# breakout.net
KiCad netlist of a schematic drawn in EAGLE
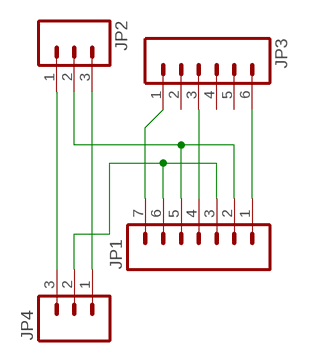
[diagram p0: schematic, sheet 1]

(export (version "E")
  (design (tool "Eeschema 10.0.6"))
  (components
    (comp (ref "JP1")
      (value "M07")
      (footprint "eagle-import:1X07")
      (libsource (lib "eagle-import") (part "M07"))
    )
    (comp (ref "JP2")
      (value "M03PTH")
      (footprint "eagle-import:1X03")
      (libsource (lib "eagle-import") (part "M03PTH"))
    )
    (comp (ref "JP3")
      (value "M06SIP")
      (footprint "eagle-import:1X06")
      (libsource (lib "eagle-import") (part "M06SIP"))
    )
    (comp (ref "JP4")
      (value "M03PTH")
      (footprint "eagle-import:1X03")
      (libsource (lib "eagle-import") (part "M03PTH"))
    )
  )
  (nets
    (net (code "1") (name "Net-(JP1-Pad1)") (class "Default")
      (node (ref "JP1") (pin "1") (pinfunction "1_1") (pintype "passive"))
      (node (ref "JP3") (pin "6") (pinfunction "6_6") (pintype "passive"))
    )
    (net (code "2") (name "Net-(JP1-Pad2)") (class "Default")
      (node (ref "JP1") (pin "2") (pinfunction "2_2") (pintype "passive"))
      (node (ref "JP1") (pin "5") (pinfunction "5_5") (pintype "passive"))
      (node (ref "JP2") (pin "2") (pinfunction "2_2") (pintype "passive"))
    )
    (net (code "3") (name "Net-(JP1-Pad3)") (class "Default")
      (node (ref "JP1") (pin "3") (pinfunction "3_3") (pintype "passive"))
      (node (ref "JP1") (pin "6") (pinfunction "6_6") (pintype "passive"))
      (node (ref "JP4") (pin "2") (pinfunction "2_2") (pintype "passive"))
    )
    (net (code "4") (name "Net-(JP1-Pad4)") (class "Default")
      (node (ref "JP1") (pin "4") (pinfunction "4_4") (pintype "passive"))
      (node (ref "JP3") (pin "3") (pinfunction "3_3") (pintype "passive"))
    )
    (net (code "5") (name "Net-(JP1-Pad7)") (class "Default")
      (node (ref "JP1") (pin "7") (pinfunction "7_7") (pintype "passive"))
      (node (ref "JP3") (pin "1") (pinfunction "1_1") (pintype "passive"))
    )
    (net (code "6") (name "Net-(JP2-Pad1)") (class "Default")
      (node (ref "JP2") (pin "1") (pinfunction "1_1") (pintype "passive"))
      (node (ref "JP4") (pin "3") (pinfunction "3_3") (pintype "passive"))
    )
    (net (code "7") (name "Net-(JP2-Pad3)") (class "Default")
      (node (ref "JP2") (pin "3") (pinfunction "3_3") (pintype "passive"))
      (node (ref "JP4") (pin "1") (pinfunction "1_1") (pintype "passive"))
    )
    (net (code "8") (name "unconnected-(JP3-Pad2)") (class "Default")
      (node (ref "JP3") (pin "2") (pinfunction "2_2") (pintype "passive"))
    )
    (net (code "9") (name "unconnected-(JP3-Pad4)") (class "Default")
      (node (ref "JP3") (pin "4") (pinfunction "4_4") (pintype "passive"))
    )
    (net (code "10") (name "unconnected-(JP3-Pad5)") (class "Default")
      (node (ref "JP3") (pin "5") (pinfunction "5_5") (pintype "passive"))
    )
  )
)
